# headset_v2.net
KiCad netlist of a schematic drawn in EAGLE
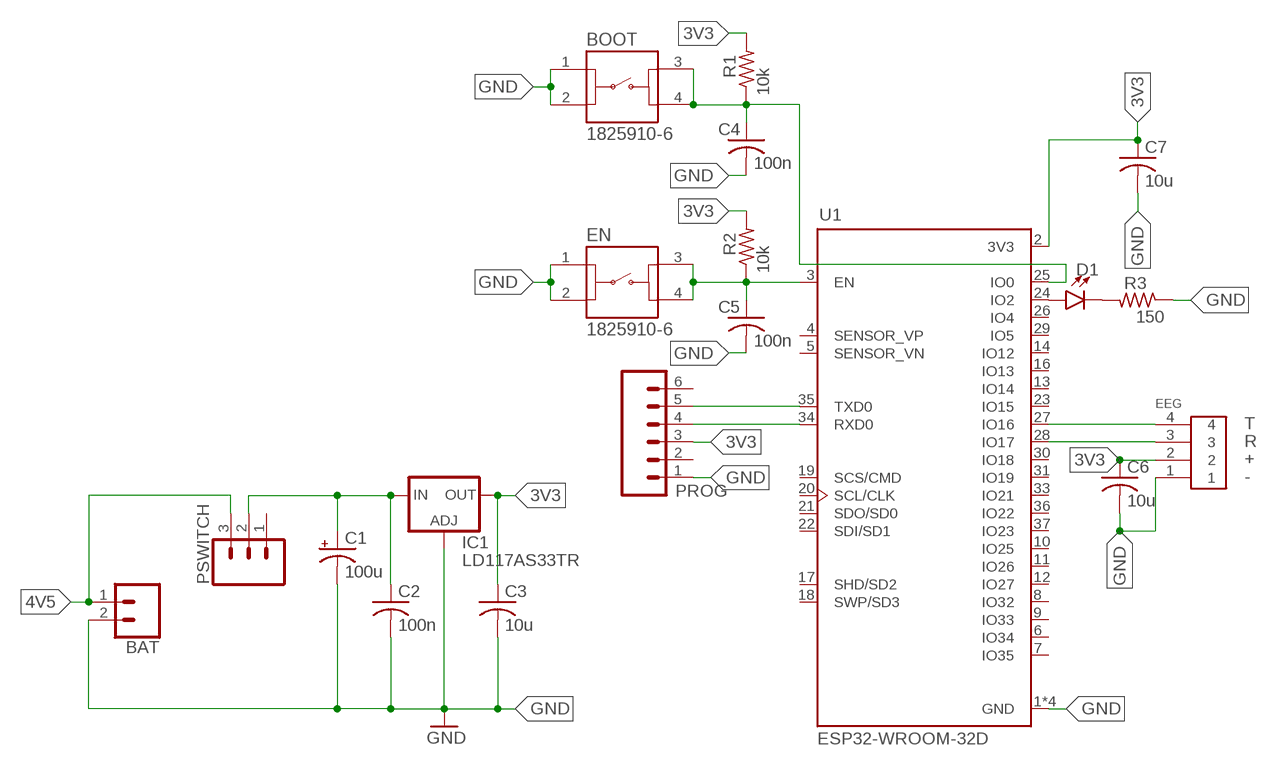
[diagram p0: schematic, sheet 1]

(export (version "E")
  (design (tool "Eeschema 10.0.6"))
  (components
    (comp (ref "BAT")
      (value "CONN_02")
      (footprint "eagle-import:1X02")
      (libsource (lib "eagle-import") (part "CONN_02"))
    )
    (comp (ref "BOOT")
      (value "1825910-6")
      (footprint "eagle-import:1825910-6")
      (fields
        (field (name "DIGIKEY_PART_NUMBER") "450-1650-ND")
        (field (name "MANUFACTURER") "TE Connectivity ALCOSWITCH Switches")
        (field (name "CREATED_BY") " PCBLayout.com")
      )
      (libsource (lib "eagle-import") (part "1825910-6"))
    )
    (comp (ref "C1")
      (value "100u")
      (footprint "eagle-import:153CLV-0810")
      (libsource (lib "eagle-import") (part "CPOL-US153CLV-0810"))
    )
    (comp (ref "C2")
      (value "100n")
      (footprint "eagle-import:C0805")
      (libsource (lib "eagle-import") (part "C-USC0805"))
    )
    (comp (ref "C3")
      (value "10u")
      (footprint "eagle-import:C0805")
      (libsource (lib "eagle-import") (part "C-USC0805"))
    )
    (comp (ref "C4")
      (value "100n")
      (footprint "eagle-import:C0805")
      (libsource (lib "eagle-import") (part "C-USC0805"))
    )
    (comp (ref "C5")
      (value "100n")
      (footprint "eagle-import:C0805")
      (libsource (lib "eagle-import") (part "C-USC0805"))
    )
    (comp (ref "C6")
      (value "10u")
      (footprint "eagle-import:C0805")
      (libsource (lib "eagle-import") (part "C-USC0805"))
    )
    (comp (ref "C7")
      (value "10u")
      (footprint "eagle-import:C0805")
      (libsource (lib "eagle-import") (part "C-USC0805"))
    )
    (comp (ref "D1")
      (value "LED3MM")
      (footprint "eagle-import:LED_3MM")
      (libsource (lib "eagle-import") (part "LED3MM"))
    )
    (comp (ref "EEG")
      (value "2PIN")
      (footprint "eagle-import:B2B-PH-K-S")
      (libsource (lib "eagle-import") (part "2PIN"))
    )
    (comp (ref "EN")
      (value "1825910-6")
      (footprint "eagle-import:1825910-6")
      (fields
        (field (name "DIGIKEY_PART_NUMBER") "450-1650-ND")
        (field (name "MANUFACTURER") "TE Connectivity ALCOSWITCH Switches")
        (field (name "CREATED_BY") " PCBLayout.com")
      )
      (libsource (lib "eagle-import") (part "1825910-6"))
    )
    (comp (ref "IC1")
      (value "LD117AS33TR")
      (footprint "eagle-import:SOT223")
      (libsource (lib "eagle-import") (part "LD117A?S33TR"))
    )
    (comp (ref "PROG")
      (value "CONN_06SILK_FEMALE_PTH")
      (footprint "eagle-import:1X06")
      (libsource (lib "eagle-import") (part "CONN_06SILK_FEMALE_PTH"))
    )
    (comp (ref "PSWITCH")
      (value "CONN_03")
      (footprint "eagle-import:1X03")
      (libsource (lib "eagle-import") (part "CONN_03"))
    )
    (comp (ref "R1")
      (value "10k")
      (footprint "eagle-import:R0805")
      (libsource (lib "eagle-import") (part "R-US_R0805"))
    )
    (comp (ref "R2")
      (value "10k")
      (footprint "eagle-import:R0805")
      (libsource (lib "eagle-import") (part "R-US_R0805"))
    )
    (comp (ref "R3")
      (value "150")
      (footprint "eagle-import:R0805")
      (libsource (lib "eagle-import") (part "R-US_R0805"))
    )
    (comp (ref "U1")
      (value "ESP32-WROOM-32D")
      (footprint "eagle-import:MODULE_ESP32-WROOM-32D")
      (fields (field (name "MF") "Espressif Systems"))
      (libsource (lib "eagle-import") (part "ESP32-WROOM-32D"))
    )
  )
  (nets
    (net (code "1") (name "3V3") (class "Default")
      (node (ref "C3") (pin "1") (pinfunction "1_1") (pintype "passive"))
      (node (ref "C6") (pin "1") (pinfunction "1_1") (pintype "passive"))
      (node (ref "C7") (pin "1") (pinfunction "1_1") (pintype "passive"))
      (node (ref "EEG") (pin "2") (pinfunction "2_2") (pintype "bidirectional"))
      (node (ref "IC1") (pin "4") (pinfunction "OUT_4") (pintype "passive"))
      (node (ref "PROG") (pin "3") (pinfunction "3_3") (pintype "passive"))
      (node (ref "R1") (pin "2") (pinfunction "2_2") (pintype "passive"))
      (node (ref "R2") (pin "2") (pinfunction "2_2") (pintype "passive"))
      (node (ref "U1") (pin "2") (pinfunction "3V3_2") (pintype "power_in"))
    )
    (net (code "2") (name "4V5") (class "Default")
      (node (ref "BAT") (pin "1") (pinfunction "1_1") (pintype "passive"))
      (node (ref "PSWITCH") (pin "3") (pinfunction "3_3") (pintype "passive"))
    )
    (net (code "3") (name "GND") (class "Default")
      (node (ref "BAT") (pin "2") (pinfunction "2_2") (pintype "passive"))
      (node (ref "BOOT") (pin "1") (pinfunction "1_1") (pintype "passive"))
      (node (ref "BOOT") (pin "2") (pinfunction "2_2") (pintype "passive"))
      (node (ref "C1") (pin "-") (pinfunction "-_-") (pintype "passive"))
      (node (ref "C2") (pin "2") (pinfunction "2_2") (pintype "passive"))
      (node (ref "C3") (pin "2") (pinfunction "2_2") (pintype "passive"))
      (node (ref "C4") (pin "2") (pinfunction "2_2") (pintype "passive"))
      (node (ref "C5") (pin "2") (pinfunction "2_2") (pintype "passive"))
      (node (ref "C6") (pin "2") (pinfunction "2_2") (pintype "passive"))
      (node (ref "C7") (pin "2") (pinfunction "2_2") (pintype "passive"))
      (node (ref "EEG") (pin "1") (pinfunction "1_1") (pintype "bidirectional"))
      (node (ref "EN") (pin "1") (pinfunction "1_1") (pintype "passive"))
      (node (ref "EN") (pin "2") (pinfunction "2_2") (pintype "passive"))
      (node (ref "IC1") (pin "1") (pinfunction "ADJ_1") (pintype "input"))
      (node (ref "PROG") (pin "1") (pinfunction "1_1") (pintype "passive"))
      (node (ref "R3") (pin "1") (pinfunction "1_1") (pintype "passive"))
      (node (ref "U1") (pin "1") (pinfunction "GND_1") (pintype "power_in"))
      (node (ref "U1") (pin "15") (pinfunction "GND_15") (pintype "power_in"))
      (node (ref "U1") (pin "38") (pinfunction "GND_38") (pintype "power_in"))
      (node (ref "U1") (pin "39") (pinfunction "GND_39") (pintype "power_in"))
    )
    (net (code "4") (name "Net-(D1-C)") (class "Default")
      (node (ref "D1") (pin "K") (pinfunction "C_K") (pintype "passive"))
      (node (ref "R3") (pin "2") (pinfunction "2_2") (pintype "passive"))
    )
    (net (code "5") (name "Net-(IC1-IN)") (class "Default")
      (node (ref "C1") (pin "+") (pinfunction "+_+") (pintype "passive"))
      (node (ref "C2") (pin "1") (pinfunction "1_1") (pintype "passive"))
      (node (ref "IC1") (pin "3") (pinfunction "IN_3") (pintype "input"))
      (node (ref "PSWITCH") (pin "2") (pinfunction "2_2") (pintype "passive"))
    )
    (net (code "6") (name "Net-(U1-EN)") (class "Default")
      (node (ref "C5") (pin "1") (pinfunction "1_1") (pintype "passive"))
      (node (ref "EN") (pin "3") (pinfunction "3_3") (pintype "passive"))
      (node (ref "EN") (pin "4") (pinfunction "4_4") (pintype "passive"))
      (node (ref "R2") (pin "1") (pinfunction "1_1") (pintype "passive"))
      (node (ref "U1") (pin "3") (pinfunction "EN_3") (pintype "input"))
    )
    (net (code "7") (name "Net-(U1-IO0)") (class "Default")
      (node (ref "BOOT") (pin "3") (pinfunction "3_3") (pintype "passive"))
      (node (ref "BOOT") (pin "4") (pinfunction "4_4") (pintype "passive"))
      (node (ref "C4") (pin "1") (pinfunction "1_1") (pintype "passive"))
      (node (ref "R1") (pin "1") (pinfunction "1_1") (pintype "passive"))
      (node (ref "U1") (pin "25") (pinfunction "IO0_25") (pintype "bidirectional"))
    )
    (net (code "8") (name "Net-(U1-IO2)") (class "Default")
      (node (ref "D1") (pin "A") (pinfunction "A_A") (pintype "passive"))
      (node (ref "U1") (pin "24") (pinfunction "IO2_24") (pintype "bidirectional"))
    )
    (net (code "9") (name "Net-(U1-IO16)") (class "Default")
      (node (ref "EEG") (pin "4") (pinfunction "4_4") (pintype "bidirectional"))
      (node (ref "U1") (pin "27") (pinfunction "IO16_27") (pintype "bidirectional"))
    )
    (net (code "10") (name "Net-(U1-IO17)") (class "Default")
      (node (ref "EEG") (pin "3") (pinfunction "3_3") (pintype "bidirectional"))
      (node (ref "U1") (pin "28") (pinfunction "IO17_28") (pintype "bidirectional"))
    )
    (net (code "11") (name "Net-(U1-RXD0)") (class "Default")
      (node (ref "PROG") (pin "4") (pinfunction "4_4") (pintype "passive"))
      (node (ref "U1") (pin "34") (pinfunction "RXD0_34") (pintype "bidirectional"))
    )
    (net (code "12") (name "Net-(U1-TXD0)") (class "Default")
      (node (ref "PROG") (pin "5") (pinfunction "5_5") (pintype "passive"))
      (node (ref "U1") (pin "35") (pinfunction "TXD0_35") (pintype "bidirectional"))
    )
    (net (code "13") (name "unconnected-(PROG-Pad2)") (class "Default")
      (node (ref "PROG") (pin "2") (pinfunction "2_2") (pintype "passive"))
    )
    (net (code "14") (name "unconnected-(PROG-Pad6)") (class "Default")
      (node (ref "PROG") (pin "6") (pinfunction "6_6") (pintype "passive"))
    )
    (net (code "15") (name "unconnected-(PSWITCH-Pad1)") (class "Default")
      (node (ref "PSWITCH") (pin "1") (pinfunction "1_1") (pintype "passive"))
    )
    (net (code "16") (name "unconnected-(U1-IO4-Pad26)") (class "Default")
      (node (ref "U1") (pin "26") (pinfunction "IO4_26") (pintype "bidirectional"))
    )
    (net (code "17") (name "unconnected-(U1-IO5-Pad29)") (class "Default")
      (node (ref "U1") (pin "29") (pinfunction "IO5_29") (pintype "bidirectional"))
    )
    (net (code "18") (name "unconnected-(U1-IO12-Pad14)") (class "Default")
      (node (ref "U1") (pin "14") (pinfunction "IO12_14") (pintype "bidirectional"))
    )
    (net (code "19") (name "unconnected-(U1-IO13-Pad16)") (class "Default")
      (node (ref "U1") (pin "16") (pinfunction "IO13_16") (pintype "bidirectional"))
    )
    (net (code "20") (name "unconnected-(U1-IO14-Pad13)") (class "Default")
      (node (ref "U1") (pin "13") (pinfunction "IO14_13") (pintype "bidirectional"))
    )
    (net (code "21") (name "unconnected-(U1-IO15-Pad23)") (class "Default")
      (node (ref "U1") (pin "23") (pinfunction "IO15_23") (pintype "bidirectional"))
    )
    (net (code "22") (name "unconnected-(U1-IO18-Pad30)") (class "Default")
      (node (ref "U1") (pin "30") (pinfunction "IO18_30") (pintype "bidirectional"))
    )
    (net (code "23") (name "unconnected-(U1-IO19-Pad31)") (class "Default")
      (node (ref "U1") (pin "31") (pinfunction "IO19_31") (pintype "bidirectional"))
    )
    (net (code "24") (name "unconnected-(U1-IO21-Pad33)") (class "Default")
      (node (ref "U1") (pin "33") (pinfunction "IO21_33") (pintype "bidirectional"))
    )
    (net (code "25") (name "unconnected-(U1-IO22-Pad36)") (class "Default")
      (node (ref "U1") (pin "36") (pinfunction "IO22_36") (pintype "bidirectional"))
    )
    (net (code "26") (name "unconnected-(U1-IO23-Pad37)") (class "Default")
      (node (ref "U1") (pin "37") (pinfunction "IO23_37") (pintype "bidirectional"))
    )
    (net (code "27") (name "unconnected-(U1-IO25-Pad10)") (class "Default")
      (node (ref "U1") (pin "10") (pinfunction "IO25_10") (pintype "bidirectional"))
    )
    (net (code "28") (name "unconnected-(U1-IO26-Pad11)") (class "Default")
      (node (ref "U1") (pin "11") (pinfunction "IO26_11") (pintype "bidirectional"))
    )
    (net (code "29") (name "unconnected-(U1-IO27-Pad12)") (class "Default")
      (node (ref "U1") (pin "12") (pinfunction "IO27_12") (pintype "bidirectional"))
    )
    (net (code "30") (name "unconnected-(U1-IO32-Pad8)") (class "Default")
      (node (ref "U1") (pin "8") (pinfunction "IO32_8") (pintype "bidirectional"))
    )
    (net (code "31") (name "unconnected-(U1-IO33-Pad9)") (class "Default")
      (node (ref "U1") (pin "9") (pinfunction "IO33_9") (pintype "bidirectional"))
    )
    (net (code "32") (name "unconnected-(U1-IO34-Pad6)") (class "Default")
      (node (ref "U1") (pin "6") (pinfunction "IO34_6") (pintype "bidirectional"))
    )
    (net (code "33") (name "unconnected-(U1-IO35-Pad7)") (class "Default")
      (node (ref "U1") (pin "7") (pinfunction "IO35_7") (pintype "bidirectional"))
    )
    (net (code "34") (name "unconnected-(U1-SCL{slash}CLK-Pad20)") (class "Default")
      (node (ref "U1") (pin "20") (pinfunction "SCL/CLK_20") (pintype "bidirectional"))
    )
    (net (code "35") (name "unconnected-(U1-SCS{slash}CMD-Pad19)") (class "Default")
      (node (ref "U1") (pin "19") (pinfunction "SCS/CMD_19") (pintype "bidirectional"))
    )
    (net (code "36") (name "unconnected-(U1-SDI{slash}SD1-Pad22)") (class "Default")
      (node (ref "U1") (pin "22") (pinfunction "SDI/SD1_22") (pintype "bidirectional"))
    )
    (net (code "37") (name "unconnected-(U1-SDO{slash}SD0-Pad21)") (class "Default")
      (node (ref "U1") (pin "21") (pinfunction "SDO/SD0_21") (pintype "bidirectional"))
    )
    (net (code "38") (name "unconnected-(U1-SENSOR_VN-Pad5)") (class "Default")
      (node (ref "U1") (pin "5") (pinfunction "SENSOR_VN_5") (pintype "input"))
    )
    (net (code "39") (name "unconnected-(U1-SENSOR_VP-Pad4)") (class "Default")
      (node (ref "U1") (pin "4") (pinfunction "SENSOR_VP_4") (pintype "input"))
    )
    (net (code "40") (name "unconnected-(U1-SHD{slash}SD2-Pad17)") (class "Default")
      (node (ref "U1") (pin "17") (pinfunction "SHD/SD2_17") (pintype "bidirectional"))
    )
    (net (code "41") (name "unconnected-(U1-SWP{slash}SD3-Pad18)") (class "Default")
      (node (ref "U1") (pin "18") (pinfunction "SWP/SD3_18") (pintype "bidirectional"))
    )
  )
)
